# CAN-Simulator_v1.net
KiCad netlist of a schematic drawn in EAGLE
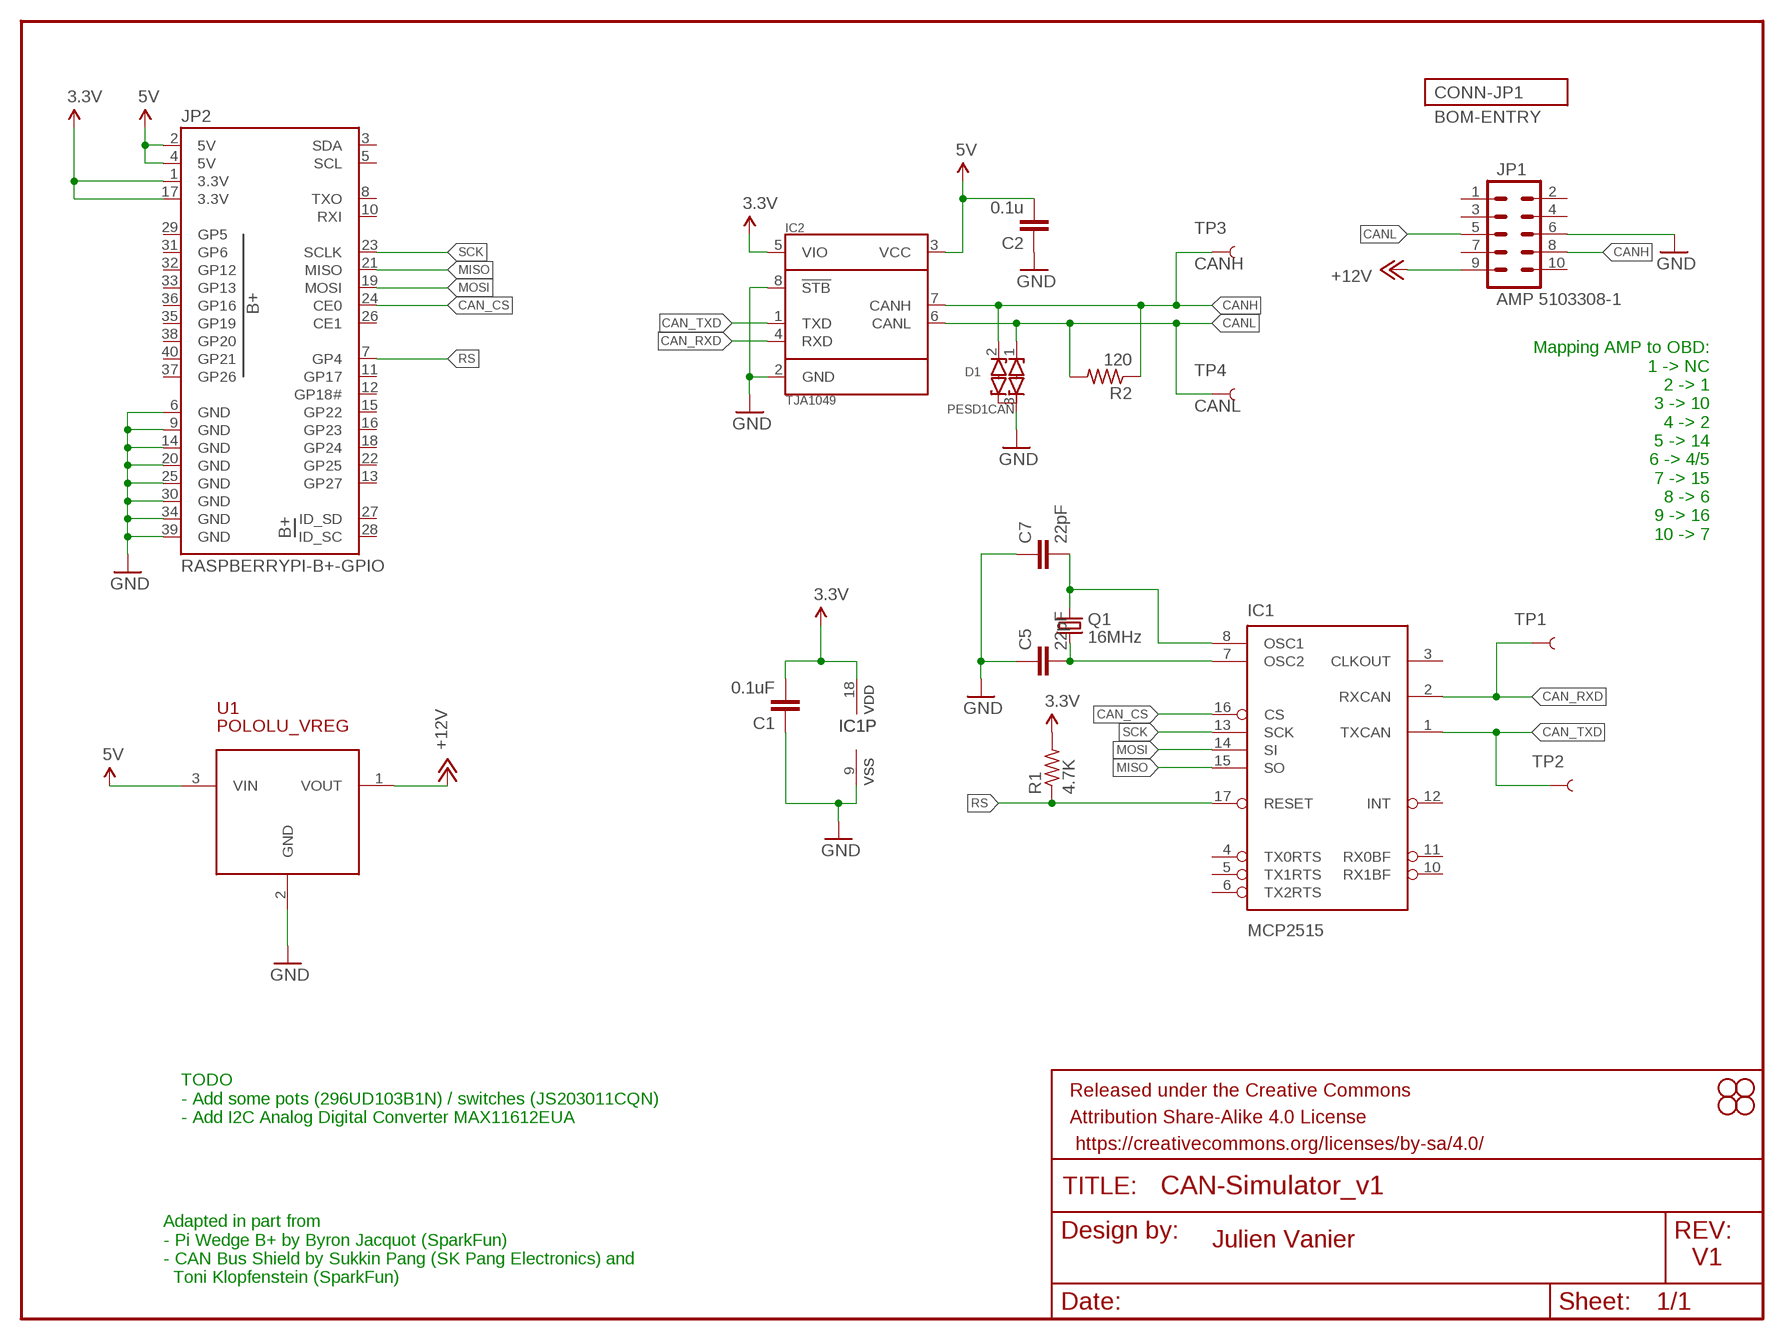
[diagram p0: schematic, sheet 1]

(export (version "E")
  (design (tool "Eeschema 10.0.6"))
  (components
    (comp (ref "C1")
      (value "0.1uF")
      (footprint "eagle-import:C0805")
      (fields (field (name "PARTNO") "08055C104KAT2A"))
      (libsource (lib "eagle-import") (part "C-EUC0805"))
    )
    (comp (ref "C2")
      (value "0.1u")
      (footprint "eagle-import:C0805")
      (fields (field (name "PARTNO") "08055C104KAT2A"))
      (libsource (lib "eagle-import") (part "C-EUC0805"))
    )
    (comp (ref "C5")
      (value "22pF")
      (footprint "eagle-import:C0805")
      (fields (field (name "PARTNO") "C0805C220J5GACTU"))
      (libsource (lib "eagle-import") (part "C-EUC0805"))
    )
    (comp (ref "C7")
      (value "22pF")
      (footprint "eagle-import:C0805")
      (fields (field (name "PARTNO") "C0805C220J5GACTU"))
      (libsource (lib "eagle-import") (part "C-EUC0805"))
    )
    (comp (ref "D1")
      (value "PESD1CAN")
      (footprint "eagle-import:SOT23")
      (fields (field (name "PARTNO") "PESD1CAN-215"))
      (libsource (lib "eagle-import") (part "DIODE_ESD_DUAL-SOT-23"))
    )
    (comp (ref "FRAME1")
      (value "FRAME-LETTER")
      (footprint "eagle-import:CREATIVE_COMMONS")
      (fields (field (name "BOM") "EXCLUDE"))
      (libsource (lib "eagle-import") (part "FRAME-LETTER"))
    )
    (comp (ref "IC1")
      (value "MCP2515")
      (footprint "eagle-import:SO-18W")
      (fields (field (name "PARTNO") "MCP2515-I/SO"))
      (libsource (lib "eagle-import") (part "MCP2510SO"))
    )
    (comp (ref "IC2")
      (value "TJA1049")
      (footprint "eagle-import:SO8")
      (fields (field (name "PARTNO") "TJA1049T-118"))
      (libsource (lib "eagle-import") (part "TJA1049"))
    )
    (comp (ref "JP1")
      (value "AMP 5103308-1")
      (footprint "eagle-import:2X5-SHROUDED")
      (fields (field (name "PARTNO") "5103308-1"))
      (libsource (lib "eagle-import") (part "M05X2SHD"))
    )
    (comp (ref "JP2")
      (value "RASPBERRYPI-B+-GPIO")
      (footprint "eagle-import:2X20-SHROUDED")
      (libsource (lib "eagle-import") (part "RASPBERRYPI-B+-GPIO"))
    )
    (comp (ref "Q1")
      (value "16MHz")
      (footprint "eagle-import:CRYSTAL-SMD-5X3")
      (fields (field (name "PARTNO") "ABM3B-16.000MHZ-10-1-U-T"))
      (libsource (lib "eagle-import") (part "CRYSTAL5X3"))
    )
    (comp (ref "R1")
      (value "4.7K")
      (footprint "eagle-import:R0805")
      (fields (field (name "PARTNO") "RC0805JR-0747KL"))
      (libsource (lib "eagle-import") (part "R-US_R0805"))
    )
    (comp (ref "R2")
      (value "120")
      (footprint "eagle-import:R0805")
      (fields (field (name "PARTNO") "RC0603FR-07120RL"))
      (libsource (lib "eagle-import") (part "R-US_R0805"))
    )
    (comp (ref "STANDOFF1")
      (value "STAND-OFFSCREW-2")
      (footprint "eagle-import:STAND-OFF-2")
      (libsource (lib "eagle-import") (part "STAND-OFFSCREW-2"))
    )
    (comp (ref "STANDOFF2")
      (value "STAND-OFFSCREW-2")
      (footprint "eagle-import:STAND-OFF-2")
      (libsource (lib "eagle-import") (part "STAND-OFFSCREW-2"))
    )
    (comp (ref "STANDOFF3")
      (value "STAND-OFFSCREW-2")
      (footprint "eagle-import:STAND-OFF-2")
      (libsource (lib "eagle-import") (part "STAND-OFFSCREW-2"))
    )
    (comp (ref "STANDOFF4")
      (value "STAND-OFFSCREW-2")
      (footprint "eagle-import:STAND-OFF-2")
      (libsource (lib "eagle-import") (part "STAND-OFFSCREW-2"))
    )
    (comp (ref "TP1")
      (value "TEST-POINT3X5")
      (footprint "eagle-import:PAD.03X.05")
      (libsource (lib "eagle-import") (part "TEST-POINT3X5"))
    )
    (comp (ref "TP2")
      (value "TEST-POINT3X5")
      (footprint "eagle-import:PAD.03X.05")
      (libsource (lib "eagle-import") (part "TEST-POINT3X5"))
    )
    (comp (ref "TP3")
      (value "CANH")
      (footprint "eagle-import:PAD.03X.03")
      (libsource (lib "eagle-import") (part "TEST-POINT3"))
    )
    (comp (ref "TP4")
      (value "CANL")
      (footprint "eagle-import:PAD.03X.03")
      (libsource (lib "eagle-import") (part "TEST-POINT3"))
    )
    (comp (ref "U1")
      (value "POLOLU_VREG")
      (footprint "eagle-import:POLOLU_VREG")
      (libsource (lib "eagle-import") (part "POLOLU_VREG"))
    )
  )
  (nets
    (net (code "1") (name "+12V") (class "Default")
      (node (ref "JP1") (pin "9") (pinfunction "9_9") (pintype "passive"))
      (node (ref "U1") (pin "1") (pinfunction "VOUT_1") (pintype "power_in"))
    )
    (net (code "2") (name "3.3V") (class "Default")
      (node (ref "C1") (pin "2") (pinfunction "2_2") (pintype "passive"))
      (node (ref "IC1") (pin "18") (pinfunction "VDD_18") (pintype "power_in"))
      (node (ref "IC2") (pin "5") (pinfunction "VIO_5") (pintype "bidirectional"))
      (node (ref "JP2") (pin "1") (pinfunction "3.3V_1") (pintype "power_in"))
      (node (ref "JP2") (pin "17") (pinfunction "3.3V_17") (pintype "power_in"))
      (node (ref "R1") (pin "2") (pinfunction "2_2") (pintype "passive"))
    )
    (net (code "3") (name "5V") (class "Default")
      (node (ref "C2") (pin "2") (pinfunction "2_2") (pintype "passive"))
      (node (ref "IC2") (pin "3") (pinfunction "VCC_3") (pintype "bidirectional"))
      (node (ref "JP2") (pin "2") (pinfunction "5V_2") (pintype "power_in"))
      (node (ref "JP2") (pin "4") (pinfunction "5V_4") (pintype "power_in"))
      (node (ref "U1") (pin "3") (pinfunction "VIN_3") (pintype "power_in"))
    )
    (net (code "4") (name "CANH") (class "Default")
      (node (ref "D1") (pin "2") (pinfunction "C2_2") (pintype "power_in"))
      (node (ref "IC2") (pin "7") (pinfunction "CANH_7") (pintype "bidirectional"))
      (node (ref "JP1") (pin "8") (pinfunction "8_8") (pintype "passive"))
      (node (ref "R2") (pin "1") (pinfunction "1_1") (pintype "passive"))
      (node (ref "TP3") (pin "P$1") (pinfunction "1_P$1") (pintype "bidirectional"))
    )
    (net (code "5") (name "CANL") (class "Default")
      (node (ref "D1") (pin "1") (pinfunction "C1_1") (pintype "power_in"))
      (node (ref "IC2") (pin "6") (pinfunction "CANL_6") (pintype "bidirectional"))
      (node (ref "JP1") (pin "5") (pinfunction "5_5") (pintype "passive"))
      (node (ref "R2") (pin "2") (pinfunction "2_2") (pintype "passive"))
      (node (ref "TP4") (pin "P$1") (pinfunction "1_P$1") (pintype "bidirectional"))
    )
    (net (code "6") (name "CAN_CS") (class "Default")
      (node (ref "IC1") (pin "16") (pinfunction "CS_16") (pintype "input"))
      (node (ref "JP2") (pin "24") (pinfunction "CE0_24") (pintype "output"))
    )
    (net (code "7") (name "CAN_RXD") (class "Default")
      (node (ref "IC1") (pin "2") (pinfunction "RXCAN_2") (pintype "input"))
      (node (ref "IC2") (pin "4") (pinfunction "RXD_4") (pintype "bidirectional"))
      (node (ref "TP1") (pin "P$1") (pinfunction "1_P$1") (pintype "bidirectional"))
    )
    (net (code "8") (name "CAN_TXD") (class "Default")
      (node (ref "IC1") (pin "1") (pinfunction "TXCAN_1") (pintype "output"))
      (node (ref "IC2") (pin "1") (pinfunction "TXD_1") (pintype "bidirectional"))
      (node (ref "TP2") (pin "P$1") (pinfunction "1_P$1") (pintype "bidirectional"))
    )
    (net (code "9") (name "GND") (class "Default")
      (node (ref "C1") (pin "1") (pinfunction "1_1") (pintype "passive"))
      (node (ref "C2") (pin "1") (pinfunction "1_1") (pintype "passive"))
      (node (ref "C5") (pin "1") (pinfunction "1_1") (pintype "passive"))
      (node (ref "C7") (pin "1") (pinfunction "1_1") (pintype "passive"))
      (node (ref "D1") (pin "3") (pinfunction "COM_3") (pintype "power_in"))
      (node (ref "IC1") (pin "9") (pinfunction "VSS_9") (pintype "power_in"))
      (node (ref "IC2") (pin "2") (pinfunction "GND_2") (pintype "bidirectional"))
      (node (ref "IC2") (pin "8") (pinfunction "~{STB}_8") (pintype "bidirectional"))
      (node (ref "JP1") (pin "6") (pinfunction "6_6") (pintype "passive"))
      (node (ref "JP2") (pin "14") (pinfunction "GND_14") (pintype "power_in"))
      (node (ref "JP2") (pin "20") (pinfunction "GND_20") (pintype "power_in"))
      (node (ref "JP2") (pin "25") (pinfunction "GND_25") (pintype "power_in"))
      (node (ref "JP2") (pin "30") (pinfunction "GND_30") (pintype "power_in"))
      (node (ref "JP2") (pin "34") (pinfunction "GND_34") (pintype "power_in"))
      (node (ref "JP2") (pin "39") (pinfunction "GND_39") (pintype "power_in"))
      (node (ref "JP2") (pin "6") (pinfunction "GND_6") (pintype "power_in"))
      (node (ref "JP2") (pin "9") (pinfunction "GND_9") (pintype "power_in"))
      (node (ref "U1") (pin "2") (pinfunction "GND_2") (pintype "power_in"))
    )
    (net (code "10") (name "MISO") (class "Default")
      (node (ref "IC1") (pin "15") (pinfunction "SO_15") (pintype "output"))
      (node (ref "JP2") (pin "21") (pinfunction "MISO_21") (pintype "input"))
    )
    (net (code "11") (name "MOSI") (class "Default")
      (node (ref "IC1") (pin "14") (pinfunction "SI_14") (pintype "input"))
      (node (ref "JP2") (pin "19") (pinfunction "MOSI_19") (pintype "output"))
    )
    (net (code "12") (name "Net-(IC1A-OSC1)") (class "Default")
      (node (ref "C7") (pin "2") (pinfunction "2_2") (pintype "passive"))
      (node (ref "IC1") (pin "8") (pinfunction "OSC1_8") (pintype "input"))
      (node (ref "Q1") (pin "3") (pinfunction "2_3") (pintype "passive"))
    )
    (net (code "13") (name "Net-(IC1A-OSC2)") (class "Default")
      (node (ref "C5") (pin "2") (pinfunction "2_2") (pintype "passive"))
      (node (ref "IC1") (pin "7") (pinfunction "OSC2_7") (pintype "output"))
      (node (ref "Q1") (pin "1") (pinfunction "1_1") (pintype "passive"))
    )
    (net (code "14") (name "RS") (class "Default")
      (node (ref "IC1") (pin "17") (pinfunction "RESET_17") (pintype "input"))
      (node (ref "JP2") (pin "7") (pinfunction "GP4_7") (pintype "bidirectional"))
      (node (ref "R1") (pin "1") (pinfunction "1_1") (pintype "passive"))
    )
    (net (code "15") (name "SCK") (class "Default")
      (node (ref "IC1") (pin "13") (pinfunction "SCK_13") (pintype "input"))
      (node (ref "JP2") (pin "23") (pinfunction "SCLK_23") (pintype "output"))
    )
    (net (code "16") (name "unconnected-(IC1A-CLKOUT-Pad3)") (class "Default")
      (node (ref "IC1") (pin "3") (pinfunction "CLKOUT_3") (pintype "output"))
    )
    (net (code "17") (name "unconnected-(IC1A-INT-Pad12)") (class "Default")
      (node (ref "IC1") (pin "12") (pinfunction "INT_12") (pintype "output"))
    )
    (net (code "18") (name "unconnected-(IC1A-RX0BF-Pad11)") (class "Default")
      (node (ref "IC1") (pin "11") (pinfunction "RX0BF_11") (pintype "output"))
    )
    (net (code "19") (name "unconnected-(IC1A-RX1BF-Pad10)") (class "Default")
      (node (ref "IC1") (pin "10") (pinfunction "RX1BF_10") (pintype "output"))
    )
    (net (code "20") (name "unconnected-(IC1A-TX0RTS-Pad4)") (class "Default")
      (node (ref "IC1") (pin "4") (pinfunction "TX0RTS_4") (pintype "input"))
    )
    (net (code "21") (name "unconnected-(IC1A-TX1RTS-Pad5)") (class "Default")
      (node (ref "IC1") (pin "5") (pinfunction "TX1RTS_5") (pintype "input"))
    )
    (net (code "22") (name "unconnected-(IC1A-TX2RTS-Pad6)") (class "Default")
      (node (ref "IC1") (pin "6") (pinfunction "TX2RTS_6") (pintype "input"))
    )
    (net (code "23") (name "unconnected-(JP1-Pad1)") (class "Default")
      (node (ref "JP1") (pin "1") (pinfunction "1_1") (pintype "passive"))
    )
    (net (code "24") (name "unconnected-(JP1-Pad2)") (class "Default")
      (node (ref "JP1") (pin "2") (pinfunction "2_2") (pintype "passive"))
    )
    (net (code "25") (name "unconnected-(JP1-Pad3)") (class "Default")
      (node (ref "JP1") (pin "3") (pinfunction "3_3") (pintype "passive"))
    )
    (net (code "26") (name "unconnected-(JP1-Pad4)") (class "Default")
      (node (ref "JP1") (pin "4") (pinfunction "4_4") (pintype "passive"))
    )
    (net (code "27") (name "unconnected-(JP1-Pad7)") (class "Default")
      (node (ref "JP1") (pin "7") (pinfunction "7_7") (pintype "passive"))
    )
    (net (code "28") (name "unconnected-(JP1-Pad10)") (class "Default")
      (node (ref "JP1") (pin "10") (pinfunction "10_10") (pintype "passive"))
    )
    (net (code "29") (name "unconnected-(JP2-CE1-Pad26)") (class "Default")
      (node (ref "JP2") (pin "26") (pinfunction "CE1_26") (pintype "output"))
    )
    (net (code "30") (name "unconnected-(JP2-GP5-Pad29)") (class "Default")
      (node (ref "JP2") (pin "29") (pinfunction "GP5_29") (pintype "bidirectional"))
    )
    (net (code "31") (name "unconnected-(JP2-GP6-Pad31)") (class "Default")
      (node (ref "JP2") (pin "31") (pinfunction "GP6_31") (pintype "bidirectional"))
    )
    (net (code "32") (name "unconnected-(JP2-GP12-Pad32)") (class "Default")
      (node (ref "JP2") (pin "32") (pinfunction "GP12_32") (pintype "bidirectional"))
    )
    (net (code "33") (name "unconnected-(JP2-GP13-Pad33)") (class "Default")
      (node (ref "JP2") (pin "33") (pinfunction "GP13_33") (pintype "bidirectional"))
    )
    (net (code "34") (name "unconnected-(JP2-GP16-Pad36)") (class "Default")
      (node (ref "JP2") (pin "36") (pinfunction "GP16_36") (pintype "bidirectional"))
    )
    (net (code "35") (name "unconnected-(JP2-GP17-Pad11)") (class "Default")
      (node (ref "JP2") (pin "11") (pinfunction "GP17_11") (pintype "bidirectional"))
    )
    (net (code "36") (name "unconnected-(JP2-GP18#-Pad12)") (class "Default")
      (node (ref "JP2") (pin "12") (pinfunction "GP18#_12") (pintype "bidirectional"))
    )
    (net (code "37") (name "unconnected-(JP2-GP19-Pad35)") (class "Default")
      (node (ref "JP2") (pin "35") (pinfunction "GP19_35") (pintype "bidirectional"))
    )
    (net (code "38") (name "unconnected-(JP2-GP20-Pad38)") (class "Default")
      (node (ref "JP2") (pin "38") (pinfunction "GP20_38") (pintype "bidirectional"))
    )
    (net (code "39") (name "unconnected-(JP2-GP21-Pad40)") (class "Default")
      (node (ref "JP2") (pin "40") (pinfunction "GP21_40") (pintype "bidirectional"))
    )
    (net (code "40") (name "unconnected-(JP2-GP22-Pad15)") (class "Default")
      (node (ref "JP2") (pin "15") (pinfunction "GP22_15") (pintype "bidirectional"))
    )
    (net (code "41") (name "unconnected-(JP2-GP23-Pad16)") (class "Default")
      (node (ref "JP2") (pin "16") (pinfunction "GP23_16") (pintype "bidirectional"))
    )
    (net (code "42") (name "unconnected-(JP2-GP24-Pad18)") (class "Default")
      (node (ref "JP2") (pin "18") (pinfunction "GP24_18") (pintype "bidirectional"))
    )
    (net (code "43") (name "unconnected-(JP2-GP25-Pad22)") (class "Default")
      (node (ref "JP2") (pin "22") (pinfunction "GP25_22") (pintype "bidirectional"))
    )
    (net (code "44") (name "unconnected-(JP2-GP26-Pad37)") (class "Default")
      (node (ref "JP2") (pin "37") (pinfunction "GP26_37") (pintype "bidirectional"))
    )
    (net (code "45") (name "unconnected-(JP2-GP27-Pad13)") (class "Default")
      (node (ref "JP2") (pin "13") (pinfunction "GP27_13") (pintype "bidirectional"))
    )
    (net (code "46") (name "unconnected-(JP2-ID_SC-Pad28)") (class "Default")
      (node (ref "JP2") (pin "28") (pinfunction "ID_SC_28") (pintype "bidirectional"))
    )
    (net (code "47") (name "unconnected-(JP2-ID_SD-Pad27)") (class "Default")
      (node (ref "JP2") (pin "27") (pinfunction "ID_SD_27") (pintype "bidirectional"))
    )
    (net (code "48") (name "unconnected-(JP2-RXI-Pad10)") (class "Default")
      (node (ref "JP2") (pin "10") (pinfunction "RXI_10") (pintype "input"))
    )
    (net (code "49") (name "unconnected-(JP2-SCL-Pad5)") (class "Default")
      (node (ref "JP2") (pin "5") (pinfunction "SCL_5") (pintype "bidirectional"))
    )
    (net (code "50") (name "unconnected-(JP2-SDA-Pad3)") (class "Default")
      (node (ref "JP2") (pin "3") (pinfunction "SDA_3") (pintype "bidirectional"))
    )
    (net (code "51") (name "unconnected-(JP2-TXO-Pad8)") (class "Default")
      (node (ref "JP2") (pin "8") (pinfunction "TXO_8") (pintype "output"))
    )
  )
)
